# razbotLowVoltageProt.net
KiCad netlist of a schematic drawn in Altium Designer
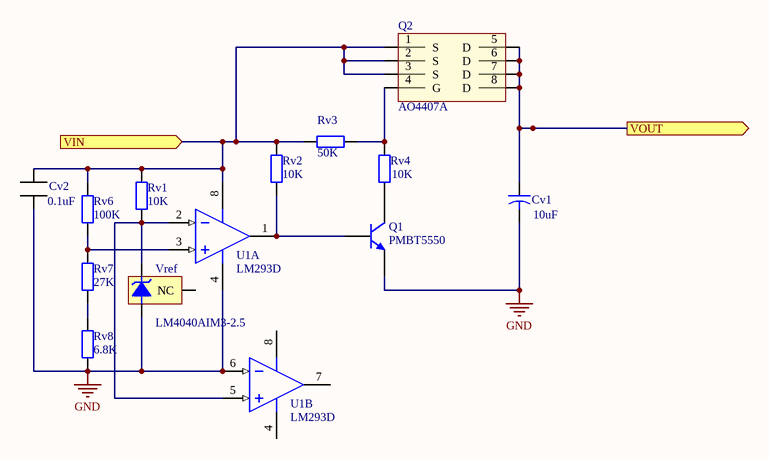
[diagram p0: razbotLowVoltageProt.SchDoc]

(export (version "E")
  (design (tool "Eeschema 10.0.6"))
  (components
    (comp (ref "Cv1")
      (value "10uF")
      (footprint "CAPR5-4X5")
      (description "Capacitor")
      (fields (field (name "Comment") "10uF EL") (field (name "PUBLISHER") "Altium Limited"))
      (libsource (lib "Miscellaneous Devices") (part "Cap2"))
    )
    (comp (ref "Cv2")
      (value "0.1uF")
      (footprint "Miscellaneous Devices:C0805")
      (description "Capacitor")
      (fields (field (name "Comment") "0.1uF 0603"))
      (libsource (lib "RpiPaw1_SchLib") (part "CAP"))
    )
    (comp (ref "Q1")
      (value "PMBT5550")
      (footprint "SOT23_M")
      (description "NPN High-voltage Transistor")
      (fields (field (name "PUBLISHER") "Altium Limited"))
      (libsource (lib "Philips Discrete BJT - Low Power") (part "PMBT5550"))
    )
    (comp (ref "Q2")
      (value "AO4407A")
      (footprint "Altera EPCS Configuration Device:SOIC8_M")
      (description "P ch MOSFET 12A")
      (libsource (lib "PiBot_SchLib") (part "AO4407A"))
    )
    (comp (ref "Rv1")
      (value "10K")
      (footprint "J1-0603")
      (description "Resistor")
      (fields (field (name "Comment") "10K 0603") (field (name "PUBLISHER") "Altium Limited"))
      (libsource (lib "Miscellaneous Devices") (part "Res2"))
    )
    (comp (ref "Rv2")
      (value "10K")
      (footprint "J1-0603")
      (description "Resistor")
      (fields (field (name "Comment") "10K 0603") (field (name "PUBLISHER") "Altium Limited"))
      (libsource (lib "Miscellaneous Devices") (part "Res2"))
    )
    (comp (ref "Rv3")
      (value "50K")
      (footprint "J1-0603")
      (description "Resistor")
      (fields (field (name "Comment") "50K 0603") (field (name "PUBLISHER") "Altium Limited"))
      (libsource (lib "") (part "Res2_2"))
    )
    (comp (ref "Rv4")
      (value "10K")
      (footprint "J1-0603")
      (description "Resistor")
      (fields (field (name "Comment") "10K 0603") (field (name "PUBLISHER") "Altium Limited"))
      (libsource (lib "") (part "Res2_1"))
    )
    (comp (ref "Rv6")
      (value "100K")
      (footprint "J1-0603")
      (description "Resistor")
      (fields (field (name "Comment") "100K 0603") (field (name "PUBLISHER") "Altium Limited"))
      (libsource (lib "Miscellaneous Devices") (part "Res2"))
    )
    (comp (ref "Rv7")
      (value "27K")
      (footprint "J1-0603")
      (description "Resistor")
      (fields (field (name "Comment") "27K 0603") (field (name "PUBLISHER") "Altium Limited"))
      (libsource (lib "Miscellaneous Devices") (part "Res2"))
    )
    (comp (ref "Rv8")
      (value "6.8K")
      (footprint "J1-0603")
      (description "Resistor")
      (fields (field (name "Comment") "6.8K 0603") (field (name "PUBLISHER") "Altium Limited"))
      (libsource (lib "Miscellaneous Devices") (part "Res2"))
    )
    (comp (ref "U1")
      (value "LM293D")
      (footprint "SO8_M")
      (description "Low-Power Dual Voltage Comparator")
      (fields (field (name "PUBLISHER") "Altium Limited"))
      (libsource (lib "ST Analog Comparator") (part "LM293D"))
    )
    (comp (ref "Vref")
      (value "LM4040AIM3-2.5")
      (footprint "MF03A_N")
      (description "Precision Micropower Shunt Voltage Reference")
      (fields
        (field (name "MANUFACTURER") "National Semiconductor")
        (field (name "DIGIKEYPARTNUMBER") "LM4040AIM3-2.5CT-ND")
        (field (name "PUBLISHER") "Altium Limited")
      )
      (libsource (lib "NSC Voltage Reference") (part "LM4040AIM3-2.5"))
    )
  )
  (nets
    (net (code "1") (name "/VIN") (class "Default")
      (node (ref "Cv2") (pin "2") (pinfunction "P2_2") (pintype "passive"))
      (node (ref "Q2") (pin "1") (pinfunction "S_1") (pintype "passive"))
      (node (ref "Q2") (pin "2") (pinfunction "S_2") (pintype "passive"))
      (node (ref "Q2") (pin "3") (pinfunction "S_3") (pintype "passive"))
      (node (ref "Rv1") (pin "1") (pinfunction "1_1") (pintype "passive"))
      (node (ref "Rv2") (pin "1") (pinfunction "1_1") (pintype "passive"))
      (node (ref "Rv3") (pin "2") (pinfunction "2_2") (pintype "passive"))
      (node (ref "Rv6") (pin "1") (pinfunction "1_1") (pintype "passive"))
      (node (ref "U1") (pin "8") (pinfunction "V+_8") (pintype "power_in"))
    )
    (net (code "2") (name "/VOUT") (class "Default")
      (node (ref "Cv1") (pin "1") (pinfunction "1_1") (pintype "passive"))
      (node (ref "Q2") (pin "5") (pinfunction "D_5") (pintype "passive"))
      (node (ref "Q2") (pin "6") (pinfunction "D_6") (pintype "passive"))
      (node (ref "Q2") (pin "7") (pinfunction "D_7") (pintype "passive"))
      (node (ref "Q2") (pin "8") (pinfunction "D_8") (pintype "passive"))
    )
    (net (code "3") (name "GND") (class "Default")
      (node (ref "Cv1") (pin "2") (pinfunction "2_2") (pintype "passive"))
      (node (ref "Cv2") (pin "1") (pinfunction "P1_1") (pintype "passive"))
      (node (ref "Q1") (pin "2") (pinfunction "E_2") (pintype "passive"))
      (node (ref "Rv8") (pin "2") (pinfunction "2_2") (pintype "passive"))
      (node (ref "U1") (pin "4") (pinfunction "V-_4") (pintype "power_in"))
      (node (ref "U1") (pin "6") (pinfunction "IN-_6") (pintype "input"))
      (node (ref "Vref") (pin "2") (pinfunction "-V_2") (pintype "passive"))
    )
    (net (code "4") (name "Net-(Q1-B)") (class "Default")
      (node (ref "Q1") (pin "1") (pinfunction "B_1") (pintype "passive"))
      (node (ref "Rv2") (pin "2") (pinfunction "2_2") (pintype "passive"))
      (node (ref "U1") (pin "1") (pinfunction "OUT_1") (pintype "open_collector"))
    )
    (net (code "5") (name "Net-(Q1-C)") (class "Default")
      (node (ref "Q1") (pin "3") (pinfunction "C_3") (pintype "passive"))
      (node (ref "Rv4") (pin "1") (pinfunction "1_1") (pintype "passive"))
    )
    (net (code "6") (name "Net-(Q2-G)") (class "Default")
      (node (ref "Q2") (pin "4") (pinfunction "G_4") (pintype "passive"))
      (node (ref "Rv3") (pin "1") (pinfunction "1_1") (pintype "passive"))
      (node (ref "Rv4") (pin "2") (pinfunction "2_2") (pintype "passive"))
    )
    (net (code "7") (name "Net-(Rv7-Pad2)") (class "Default")
      (node (ref "Rv7") (pin "2") (pinfunction "2_2") (pintype "passive"))
      (node (ref "Rv8") (pin "1") (pinfunction "1_1") (pintype "passive"))
    )
    (net (code "8") (name "Net-(U1A-IN+)") (class "Default")
      (node (ref "Rv6") (pin "2") (pinfunction "2_2") (pintype "passive"))
      (node (ref "Rv7") (pin "1") (pinfunction "1_1") (pintype "passive"))
      (node (ref "U1") (pin "3") (pinfunction "IN+_3") (pintype "input"))
    )
    (net (code "9") (name "Net-(U1A-IN-)") (class "Default")
      (node (ref "Rv1") (pin "2") (pinfunction "2_2") (pintype "passive"))
      (node (ref "U1") (pin "2") (pinfunction "IN-_2") (pintype "input"))
      (node (ref "U1") (pin "5") (pinfunction "IN+_5") (pintype "input"))
      (node (ref "Vref") (pin "1") (pinfunction "+V_1") (pintype "passive"))
    )
    (net (code "10") (name "unconnected-(U1B-OUT-Pad7)") (class "Default")
      (node (ref "U1") (pin "7") (pinfunction "OUT_7") (pintype "open_collector"))
    )
    (net (code "11") (name "unconnected-(U1B-V+-Pad8)") (class "Default")
      (node (ref "U1") (pin "8") (pinfunction "V+_8") (pintype "power_in"))
    )
    (net (code "12") (name "unconnected-(U1B-V--Pad4)") (class "Default")
      (node (ref "U1") (pin "4") (pinfunction "V-_4") (pintype "power_in"))
    )
    (net (code "13") (name "unconnected-(Vref-NC-Pad3)") (class "Default")
      (node (ref "Vref") (pin "3") (pinfunction "NC_3") (pintype "passive"))
    )
  )
)
